# vusb-i2c-tht.net
KiCad netlist of a schematic drawn in EAGLE
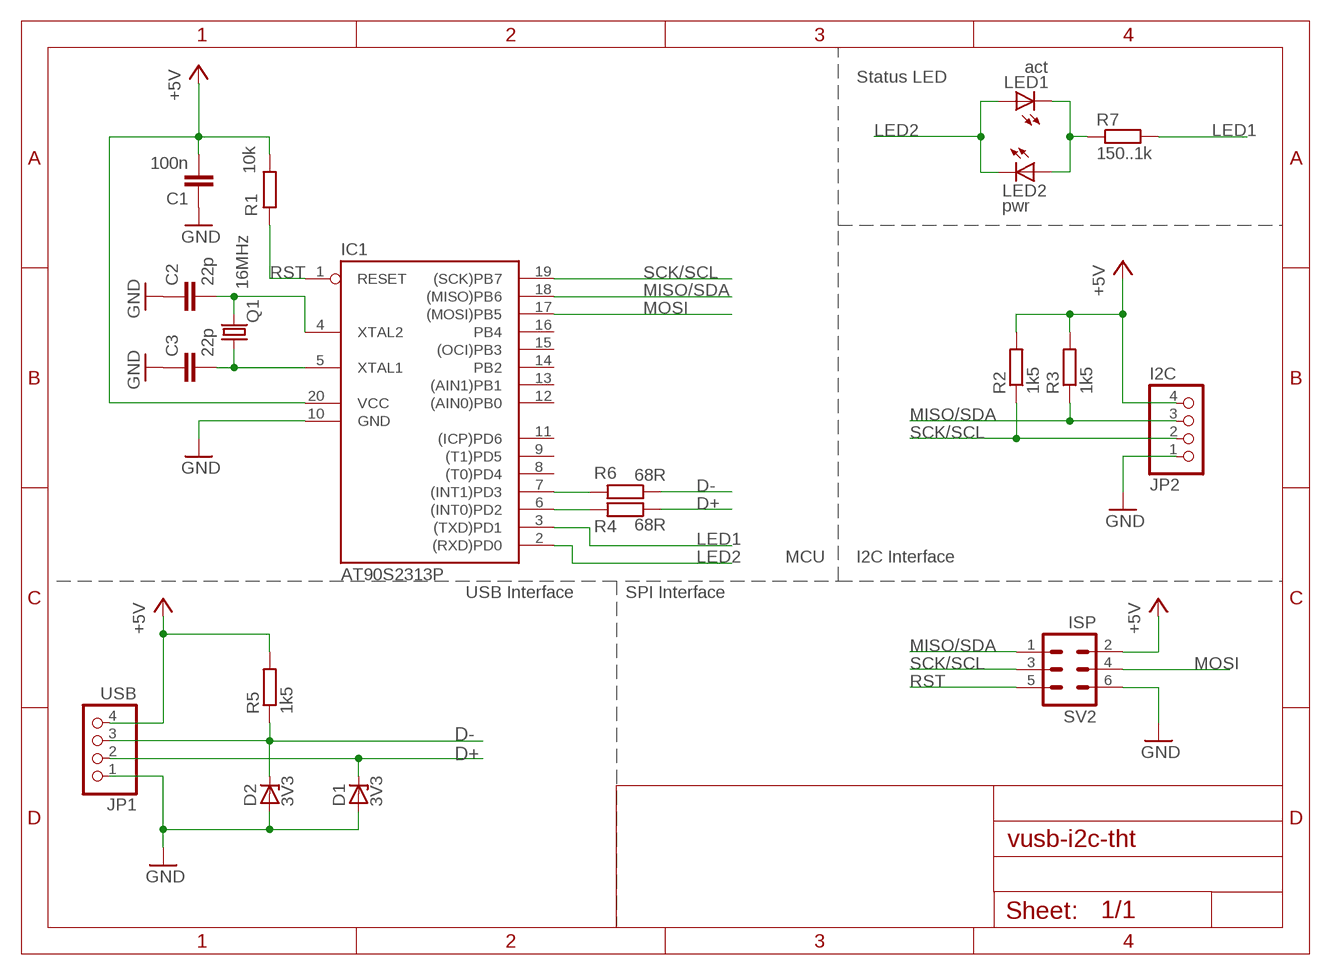
[diagram p0: schematic, sheet 1]

(export (version "E")
  (design (tool "Eeschema 10.0.6"))
  (components
    (comp (ref "C1")
      (value "100n")
      (footprint "eagle-import:C0805")
      (libsource (lib "eagle-import") (part "C-EUC0805"))
    )
    (comp (ref "C2")
      (value "22p")
      (footprint "eagle-import:C0805")
      (libsource (lib "eagle-import") (part "C-EUC0805"))
    )
    (comp (ref "C3")
      (value "22p")
      (footprint "eagle-import:C0805")
      (libsource (lib "eagle-import") (part "C-EUC0805"))
    )
    (comp (ref "D1")
      (value "3V3")
      (footprint "eagle-import:DO34Z7")
      (libsource (lib "eagle-import") (part "ZENER-DIODEDO34-7"))
    )
    (comp (ref "D2")
      (value "3V3")
      (footprint "eagle-import:DO34Z7")
      (libsource (lib "eagle-import") (part "ZENER-DIODEDO34-7"))
    )
    (comp (ref "IC1")
      (value "AT90S2313P")
      (footprint "eagle-import:DIL20")
      (libsource (lib "eagle-import") (part "AT90S2313P"))
    )
    (comp (ref "JP1")
      (value "USB")
      (footprint "eagle-import:1X04")
      (libsource (lib "eagle-import") (part "PINHD-1X4"))
    )
    (comp (ref "JP2")
      (value "I2C")
      (footprint "eagle-import:1X04")
      (libsource (lib "eagle-import") (part "PINHD-1X4"))
    )
    (comp (ref "LED1")
      (value "act")
      (footprint "eagle-import:LED3MM")
      (libsource (lib "eagle-import") (part "LED3MM"))
    )
    (comp (ref "LED2")
      (value "pwr")
      (footprint "eagle-import:LED3MM")
      (libsource (lib "eagle-import") (part "LED3MM"))
    )
    (comp (ref "Q1")
      (value "16MHz")
      (footprint "eagle-import:HC49_S")
      (libsource (lib "eagle-import") (part "CRYTALHC49S"))
    )
    (comp (ref "R1")
      (value "10k")
      (footprint "eagle-import:0207_10")
      (libsource (lib "eagle-import") (part "R-EU_0207/10"))
    )
    (comp (ref "R2")
      (value "1k5")
      (footprint "eagle-import:0207_10")
      (libsource (lib "eagle-import") (part "R-EU_0207/10"))
    )
    (comp (ref "R3")
      (value "1k5")
      (footprint "eagle-import:0207_10")
      (libsource (lib "eagle-import") (part "R-EU_0207/10"))
    )
    (comp (ref "R4")
      (value "68R")
      (footprint "eagle-import:0207_10")
      (libsource (lib "eagle-import") (part "R-EU_0207/10"))
    )
    (comp (ref "R5")
      (value "1k5")
      (footprint "eagle-import:0207_10")
      (libsource (lib "eagle-import") (part "R-EU_0207/10"))
    )
    (comp (ref "R6")
      (value "68R")
      (footprint "eagle-import:0207_10")
      (libsource (lib "eagle-import") (part "R-EU_0207/10"))
    )
    (comp (ref "R7")
      (value "150..1k")
      (footprint "eagle-import:0207_10")
      (libsource (lib "eagle-import") (part "R-EU_0207/10"))
    )
    (comp (ref "SV2")
      (value "ISP")
      (footprint "eagle-import:ML6")
      (libsource (lib "eagle-import") (part "ML6"))
    )
  )
  (nets
    (net (code "1") (name "+5V") (class "Default")
      (node (ref "C1") (pin "2") (pinfunction "2_2") (pintype "passive"))
      (node (ref "IC1") (pin "20") (pinfunction "VCC_20") (pintype "power_in"))
      (node (ref "JP1") (pin "4") (pinfunction "4_4") (pintype "passive"))
      (node (ref "JP2") (pin "4") (pinfunction "4_4") (pintype "passive"))
      (node (ref "R1") (pin "2") (pinfunction "2_2") (pintype "passive"))
      (node (ref "R2") (pin "2") (pinfunction "2_2") (pintype "passive"))
      (node (ref "R3") (pin "2") (pinfunction "2_2") (pintype "passive"))
      (node (ref "R5") (pin "2") (pinfunction "2_2") (pintype "passive"))
      (node (ref "SV2") (pin "2") (pinfunction "2_2") (pintype "passive"))
    )
    (net (code "2") (name "/D+") (class "Default")
      (node (ref "D1") (pin "C") (pinfunction "C_C") (pintype "passive"))
      (node (ref "JP1") (pin "2") (pinfunction "2_2") (pintype "passive"))
      (node (ref "R4") (pin "1") (pinfunction "1_1") (pintype "passive"))
    )
    (net (code "3") (name "/D-") (class "Default")
      (node (ref "D2") (pin "C") (pinfunction "C_C") (pintype "passive"))
      (node (ref "JP1") (pin "3") (pinfunction "3_3") (pintype "passive"))
      (node (ref "R5") (pin "1") (pinfunction "1_1") (pintype "passive"))
      (node (ref "R6") (pin "1") (pinfunction "1_1") (pintype "passive"))
    )
    (net (code "4") (name "/LED1") (class "Default")
      (node (ref "IC1") (pin "3") (pinfunction "(TXD)PD1_3") (pintype "bidirectional"))
      (node (ref "R7") (pin "2") (pinfunction "2_2") (pintype "passive"))
    )
    (net (code "5") (name "/LED2") (class "Default")
      (node (ref "IC1") (pin "2") (pinfunction "(RXD)PD0_2") (pintype "bidirectional"))
      (node (ref "LED1") (pin "A") (pinfunction "A_A") (pintype "passive"))
      (node (ref "LED2") (pin "K") (pinfunction "C_K") (pintype "passive"))
    )
    (net (code "6") (name "/MISO{slash}SDA") (class "Default")
      (node (ref "IC1") (pin "18") (pinfunction "(MISO)PB6_18") (pintype "bidirectional"))
      (node (ref "JP2") (pin "3") (pinfunction "3_3") (pintype "passive"))
      (node (ref "R3") (pin "1") (pinfunction "1_1") (pintype "passive"))
      (node (ref "SV2") (pin "1") (pinfunction "1_1") (pintype "passive"))
    )
    (net (code "7") (name "/MOSI") (class "Default")
      (node (ref "IC1") (pin "17") (pinfunction "(MOSI)PB5_17") (pintype "bidirectional"))
      (node (ref "SV2") (pin "4") (pinfunction "4_4") (pintype "passive"))
    )
    (net (code "8") (name "/RST") (class "Default")
      (node (ref "IC1") (pin "1") (pinfunction "RESET_1") (pintype "bidirectional"))
      (node (ref "R1") (pin "1") (pinfunction "1_1") (pintype "passive"))
      (node (ref "SV2") (pin "5") (pinfunction "5_5") (pintype "passive"))
    )
    (net (code "9") (name "/SCK{slash}SCL") (class "Default")
      (node (ref "IC1") (pin "19") (pinfunction "(SCK)PB7_19") (pintype "bidirectional"))
      (node (ref "JP2") (pin "2") (pinfunction "2_2") (pintype "passive"))
      (node (ref "R2") (pin "1") (pinfunction "1_1") (pintype "passive"))
      (node (ref "SV2") (pin "3") (pinfunction "3_3") (pintype "passive"))
    )
    (net (code "10") (name "GND") (class "Default")
      (node (ref "C1") (pin "1") (pinfunction "1_1") (pintype "passive"))
      (node (ref "C2") (pin "1") (pinfunction "1_1") (pintype "passive"))
      (node (ref "C3") (pin "1") (pinfunction "1_1") (pintype "passive"))
      (node (ref "D1") (pin "A") (pinfunction "A_A") (pintype "passive"))
      (node (ref "D2") (pin "A") (pinfunction "A_A") (pintype "passive"))
      (node (ref "IC1") (pin "10") (pinfunction "GND_10") (pintype "power_in"))
      (node (ref "JP1") (pin "1") (pinfunction "1_1") (pintype "passive"))
      (node (ref "JP2") (pin "1") (pinfunction "1_1") (pintype "passive"))
      (node (ref "SV2") (pin "6") (pinfunction "6_6") (pintype "passive"))
    )
    (net (code "11") (name "Net-(IC1-(INT0)PD2)") (class "Default")
      (node (ref "IC1") (pin "6") (pinfunction "(INT0)PD2_6") (pintype "bidirectional"))
      (node (ref "R4") (pin "2") (pinfunction "2_2") (pintype "passive"))
    )
    (net (code "12") (name "Net-(IC1-(INT1)PD3)") (class "Default")
      (node (ref "IC1") (pin "7") (pinfunction "(INT1)PD3_7") (pintype "bidirectional"))
      (node (ref "R6") (pin "2") (pinfunction "2_2") (pintype "passive"))
    )
    (net (code "13") (name "Net-(IC1-XTAL1)") (class "Default")
      (node (ref "C3") (pin "2") (pinfunction "2_2") (pintype "passive"))
      (node (ref "IC1") (pin "5") (pinfunction "XTAL1_5") (pintype "bidirectional"))
      (node (ref "Q1") (pin "1") (pinfunction "1_1") (pintype "passive"))
    )
    (net (code "14") (name "Net-(IC1-XTAL2)") (class "Default")
      (node (ref "C2") (pin "2") (pinfunction "2_2") (pintype "passive"))
      (node (ref "IC1") (pin "4") (pinfunction "XTAL2_4") (pintype "bidirectional"))
      (node (ref "Q1") (pin "2") (pinfunction "2_2") (pintype "passive"))
    )
    (net (code "15") (name "Net-(LED1-C)") (class "Default")
      (node (ref "LED1") (pin "K") (pinfunction "C_K") (pintype "passive"))
      (node (ref "LED2") (pin "A") (pinfunction "A_A") (pintype "passive"))
      (node (ref "R7") (pin "1") (pinfunction "1_1") (pintype "passive"))
    )
    (net (code "16") (name "unconnected-(IC1-(AIN0)PB0-Pad12)") (class "Default")
      (node (ref "IC1") (pin "12") (pinfunction "(AIN0)PB0_12") (pintype "bidirectional"))
    )
    (net (code "17") (name "unconnected-(IC1-(AIN1)PB1-Pad13)") (class "Default")
      (node (ref "IC1") (pin "13") (pinfunction "(AIN1)PB1_13") (pintype "bidirectional"))
    )
    (net (code "18") (name "unconnected-(IC1-(ICP)PD6-Pad11)") (class "Default")
      (node (ref "IC1") (pin "11") (pinfunction "(ICP)PD6_11") (pintype "bidirectional"))
    )
    (net (code "19") (name "unconnected-(IC1-(OCI)PB3-Pad15)") (class "Default")
      (node (ref "IC1") (pin "15") (pinfunction "(OCI)PB3_15") (pintype "bidirectional"))
    )
    (net (code "20") (name "unconnected-(IC1-(T0)PD4-Pad8)") (class "Default")
      (node (ref "IC1") (pin "8") (pinfunction "(T0)PD4_8") (pintype "bidirectional"))
    )
    (net (code "21") (name "unconnected-(IC1-(T1)PD5-Pad9)") (class "Default")
      (node (ref "IC1") (pin "9") (pinfunction "(T1)PD5_9") (pintype "bidirectional"))
    )
    (net (code "22") (name "unconnected-(IC1-PB2-Pad14)") (class "Default")
      (node (ref "IC1") (pin "14") (pinfunction "PB2_14") (pintype "bidirectional"))
    )
    (net (code "23") (name "unconnected-(IC1-PB4-Pad16)") (class "Default")
      (node (ref "IC1") (pin "16") (pinfunction "PB4_16") (pintype "bidirectional"))
    )
  )
)
